# analog.net
KiCad netlist of a schematic drawn in EAGLE
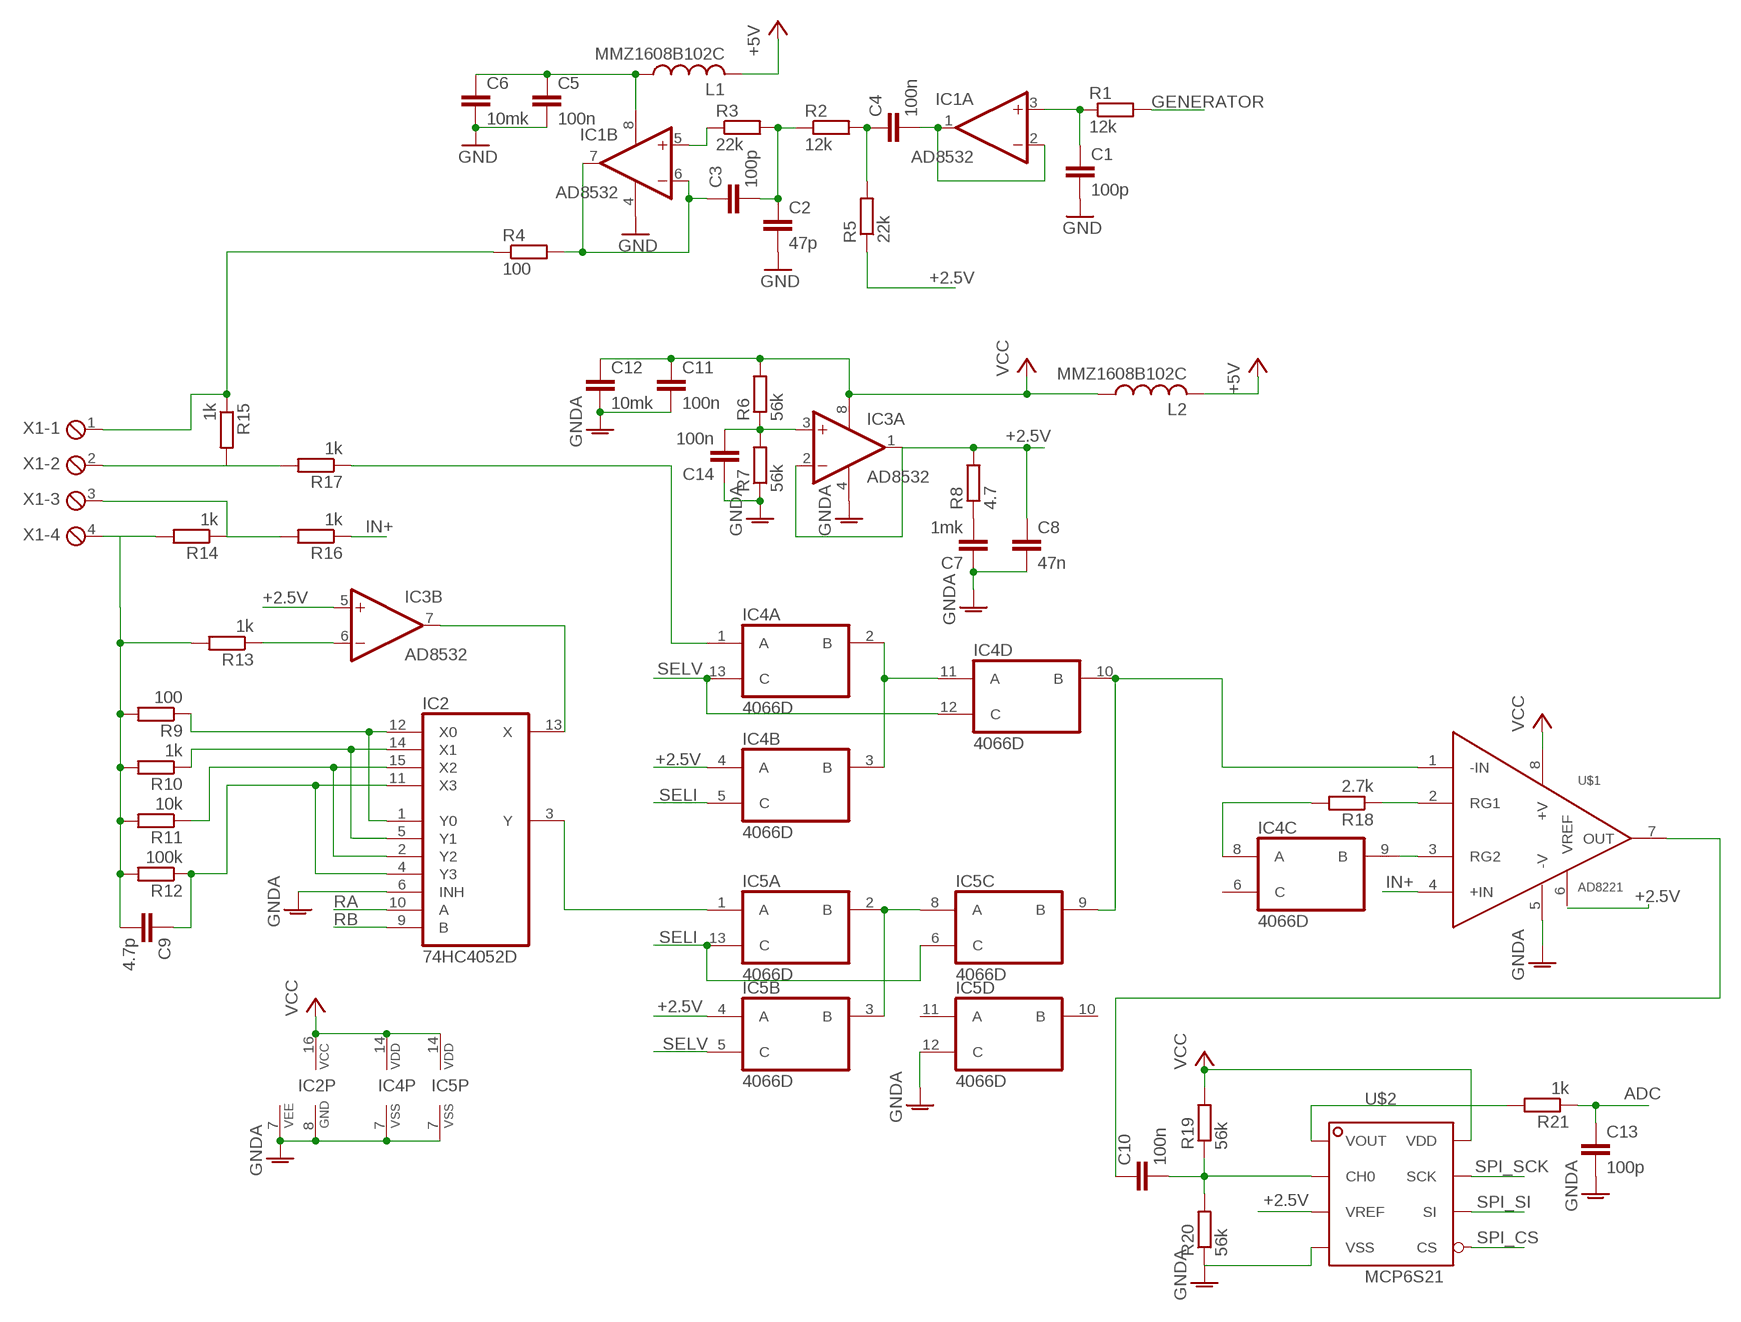
[diagram p0: schematic, sheet 1]

(export (version "E")
  (design (tool "Eeschema 10.0.6"))
  (components
    (comp (ref "C1")
      (value "100p")
      (footprint "eagle-import:C0805")
      (libsource (lib "eagle-import") (part "C-EUC0805"))
    )
    (comp (ref "C2")
      (value "47p")
      (footprint "eagle-import:C0805")
      (libsource (lib "eagle-import") (part "C-EUC0805"))
    )
    (comp (ref "C3")
      (value "100p")
      (footprint "eagle-import:C0805")
      (libsource (lib "eagle-import") (part "C-EUC0805"))
    )
    (comp (ref "C4")
      (value "100n")
      (footprint "eagle-import:C0603")
      (libsource (lib "eagle-import") (part "C-EUC0603"))
    )
    (comp (ref "C5")
      (value "100n")
      (footprint "eagle-import:C0603")
      (libsource (lib "eagle-import") (part "C-EUC0603"))
    )
    (comp (ref "C6")
      (value "10mk")
      (footprint "eagle-import:C0805")
      (libsource (lib "eagle-import") (part "C-EUC0805"))
    )
    (comp (ref "C7")
      (value "1mk")
      (footprint "eagle-import:C0603")
      (libsource (lib "eagle-import") (part "C-EUC0603"))
    )
    (comp (ref "C8")
      (value "47n")
      (footprint "eagle-import:C0805")
      (libsource (lib "eagle-import") (part "C-EUC0805"))
    )
    (comp (ref "C9")
      (value "4.7p")
      (footprint "eagle-import:C0805")
      (libsource (lib "eagle-import") (part "C-EUC0805"))
    )
    (comp (ref "C10")
      (value "100n")
      (footprint "eagle-import:C0603")
      (libsource (lib "eagle-import") (part "C-EUC0603"))
    )
    (comp (ref "C11")
      (value "100n")
      (footprint "eagle-import:C0603")
      (libsource (lib "eagle-import") (part "C-EUC0603"))
    )
    (comp (ref "C12")
      (value "10mk")
      (footprint "eagle-import:C0805")
      (libsource (lib "eagle-import") (part "C-EUC0805"))
    )
    (comp (ref "C13")
      (value "100p")
      (footprint "eagle-import:C0805")
      (libsource (lib "eagle-import") (part "C-EUC0805"))
    )
    (comp (ref "C14")
      (value "100n")
      (footprint "eagle-import:C0603")
      (libsource (lib "eagle-import") (part "C-EUC0603"))
    )
    (comp (ref "IC1")
      (value "AD8532")
      (footprint "eagle-import:SO08")
      (libsource (lib "eagle-import") (part "LM358D"))
    )
    (comp (ref "IC2")
      (value "74HC4052D")
      (footprint "eagle-import:SO16")
      (libsource (lib "eagle-import") (part "4052D"))
    )
    (comp (ref "IC3")
      (value "AD8532")
      (footprint "eagle-import:SO08")
      (libsource (lib "eagle-import") (part "LM358D"))
    )
    (comp (ref "IC4")
      (value "4066D")
      (footprint "eagle-import:SO14")
      (libsource (lib "eagle-import") (part "4066D"))
    )
    (comp (ref "IC5")
      (value "4066D")
      (footprint "eagle-import:SO14")
      (libsource (lib "eagle-import") (part "4066D"))
    )
    (comp (ref "L1")
      (value "MMZ1608B102C")
      (footprint "eagle-import:R0603")
      (libsource (lib "eagle-import") (part "L-US"))
    )
    (comp (ref "L2")
      (value "MMZ1608B102C")
      (footprint "eagle-import:R0603")
      (libsource (lib "eagle-import") (part "L-US"))
    )
    (comp (ref "R1")
      (value "12k")
      (footprint "eagle-import:R0805")
      (libsource (lib "eagle-import") (part "R-EU_R0805"))
    )
    (comp (ref "R2")
      (value "12k")
      (footprint "eagle-import:R0805")
      (libsource (lib "eagle-import") (part "R-EU_R0805"))
    )
    (comp (ref "R3")
      (value "22k")
      (footprint "eagle-import:R0805")
      (libsource (lib "eagle-import") (part "R-EU_R0805"))
    )
    (comp (ref "R4")
      (value "100")
      (footprint "eagle-import:R0805")
      (libsource (lib "eagle-import") (part "R-EU_R0805"))
    )
    (comp (ref "R5")
      (value "22k")
      (footprint "eagle-import:R0805")
      (libsource (lib "eagle-import") (part "R-EU_R0805"))
    )
    (comp (ref "R6")
      (value "56k")
      (footprint "eagle-import:R0805")
      (libsource (lib "eagle-import") (part "R-EU_R0805"))
    )
    (comp (ref "R7")
      (value "56k")
      (footprint "eagle-import:R0805")
      (libsource (lib "eagle-import") (part "R-EU_R0805"))
    )
    (comp (ref "R8")
      (value "4.7")
      (footprint "eagle-import:R0805")
      (libsource (lib "eagle-import") (part "R-EU_R0805"))
    )
    (comp (ref "R9")
      (value "100")
      (footprint "eagle-import:R0805")
      (libsource (lib "eagle-import") (part "R-EU_R0805"))
    )
    (comp (ref "R10")
      (value "1k")
      (footprint "eagle-import:R0805")
      (libsource (lib "eagle-import") (part "R-EU_R0805"))
    )
    (comp (ref "R11")
      (value "10k")
      (footprint "eagle-import:R0805")
      (libsource (lib "eagle-import") (part "R-EU_R0805"))
    )
    (comp (ref "R12")
      (value "100k")
      (footprint "eagle-import:R0805")
      (libsource (lib "eagle-import") (part "R-EU_R0805"))
    )
    (comp (ref "R13")
      (value "1k")
      (footprint "eagle-import:R0805")
      (libsource (lib "eagle-import") (part "R-EU_R0805"))
    )
    (comp (ref "R14")
      (value "1k")
      (footprint "eagle-import:R0805")
      (libsource (lib "eagle-import") (part "R-EU_R0805"))
    )
    (comp (ref "R15")
      (value "1k")
      (footprint "eagle-import:R0805")
      (libsource (lib "eagle-import") (part "R-EU_R0805"))
    )
    (comp (ref "R16")
      (value "1k")
      (footprint "eagle-import:R0805")
      (libsource (lib "eagle-import") (part "R-EU_R0805"))
    )
    (comp (ref "R17")
      (value "1k")
      (footprint "eagle-import:R0805")
      (libsource (lib "eagle-import") (part "R-EU_R0805"))
    )
    (comp (ref "R18")
      (value "2.7k")
      (footprint "eagle-import:R0805")
      (libsource (lib "eagle-import") (part "R-EU_R0805"))
    )
    (comp (ref "R19")
      (value "56k")
      (footprint "eagle-import:R0805")
      (libsource (lib "eagle-import") (part "R-EU_R0805"))
    )
    (comp (ref "R20")
      (value "56k")
      (footprint "eagle-import:R0805")
      (libsource (lib "eagle-import") (part "R-EU_R0805"))
    )
    (comp (ref "R21")
      (value "1k")
      (footprint "eagle-import:R0805")
      (libsource (lib "eagle-import") (part "R-EU_R0805"))
    )
    (comp (ref "U$1")
      (value "AD8221")
      (footprint "eagle-import:SSOP08")
      (libsource (lib "eagle-import") (part "AD8221"))
    )
    (comp (ref "U$2")
      (value "MCP6S21")
      (footprint "eagle-import:SO8")
      (libsource (lib "eagle-import") (part "MCP6S21"))
    )
    (comp (ref "X1")
      (value "MPT4")
      (footprint "eagle-import:4POL254")
      (libsource (lib "eagle-import") (part "MPT4"))
    )
  )
  (nets
    (net (code "1") (name "+5V") (class "Default")
      (node (ref "L1") (pin "2") (pinfunction "2_2") (pintype "passive"))
      (node (ref "L2") (pin "2") (pinfunction "2_2") (pintype "passive"))
    )
    (net (code "2") (name "/+2.5V") (class "Default")
      (node (ref "C8") (pin "1") (pinfunction "1_1") (pintype "passive"))
      (node (ref "IC3") (pin "1") (pinfunction "OUT_1") (pintype "output"))
      (node (ref "IC3") (pin "2") (pinfunction "-IN_2") (pintype "input"))
      (node (ref "IC3") (pin "5") (pinfunction "+IN_5") (pintype "input"))
      (node (ref "IC4") (pin "4") (pinfunction "A_4") (pintype "tri_state"))
      (node (ref "IC5") (pin "4") (pinfunction "A_4") (pintype "tri_state"))
      (node (ref "R5") (pin "1") (pinfunction "1_1") (pintype "passive"))
      (node (ref "R8") (pin "2") (pinfunction "2_2") (pintype "passive"))
      (node (ref "U$2") (pin "3") (pinfunction "VREF_3") (pintype "bidirectional"))
    )
    (net (code "3") (name "/ADC") (class "Default")
      (node (ref "C13") (pin "1") (pinfunction "1_1") (pintype "passive"))
      (node (ref "R21") (pin "1") (pinfunction "1_1") (pintype "passive"))
    )
    (net (code "4") (name "/GENERATOR") (class "Default")
      (node (ref "R1") (pin "2") (pinfunction "2_2") (pintype "passive"))
    )
    (net (code "5") (name "/IN+") (class "Default")
      (node (ref "R16") (pin "1") (pinfunction "1_1") (pintype "passive"))
      (node (ref "U$1") (pin "4") (pinfunction "+IN_4") (pintype "bidirectional"))
    )
    (net (code "6") (name "/RA") (class "Default")
      (node (ref "IC2") (pin "10") (pinfunction "A_10") (pintype "input"))
    )
    (net (code "7") (name "/RB") (class "Default")
      (node (ref "IC2") (pin "9") (pinfunction "B_9") (pintype "input"))
    )
    (net (code "8") (name "/SELI") (class "Default")
      (node (ref "IC4") (pin "5") (pinfunction "C_5") (pintype "input"))
      (node (ref "IC5") (pin "13") (pinfunction "C_13") (pintype "input"))
      (node (ref "IC5") (pin "6") (pinfunction "C_6") (pintype "input"))
    )
    (net (code "9") (name "/SELV") (class "Default")
      (node (ref "IC4") (pin "12") (pinfunction "C_12") (pintype "input"))
      (node (ref "IC4") (pin "13") (pinfunction "C_13") (pintype "input"))
      (node (ref "IC5") (pin "5") (pinfunction "C_5") (pintype "input"))
    )
    (net (code "10") (name "/SPI_CS") (class "Default")
      (node (ref "U$2") (pin "5") (pinfunction "CS_5") (pintype "bidirectional"))
    )
    (net (code "11") (name "/SPI_SCK") (class "Default")
      (node (ref "U$2") (pin "7") (pinfunction "SCK_7") (pintype "bidirectional"))
    )
    (net (code "12") (name "/SPI_SI") (class "Default")
      (node (ref "U$2") (pin "6") (pinfunction "SI_6") (pintype "bidirectional"))
    )
    (net (code "13") (name "GND") (class "Default")
      (node (ref "C1") (pin "2") (pinfunction "2_2") (pintype "passive"))
      (node (ref "C2") (pin "2") (pinfunction "2_2") (pintype "passive"))
      (node (ref "C5") (pin "2") (pinfunction "2_2") (pintype "passive"))
      (node (ref "C6") (pin "2") (pinfunction "2_2") (pintype "passive"))
      (node (ref "IC1") (pin "4") (pinfunction "V-_4") (pintype "power_in"))
    )
    (net (code "14") (name "GNDA") (class "Default")
      (node (ref "C11") (pin "2") (pinfunction "2_2") (pintype "passive"))
      (node (ref "C12") (pin "2") (pinfunction "2_2") (pintype "passive"))
      (node (ref "C13") (pin "2") (pinfunction "2_2") (pintype "passive"))
      (node (ref "C14") (pin "1") (pinfunction "1_1") (pintype "passive"))
      (node (ref "C7") (pin "1") (pinfunction "1_1") (pintype "passive"))
      (node (ref "C8") (pin "2") (pinfunction "2_2") (pintype "passive"))
      (node (ref "IC2") (pin "6") (pinfunction "INH_6") (pintype "input"))
      (node (ref "IC2") (pin "7") (pinfunction "VEE_7") (pintype "power_in"))
      (node (ref "IC2") (pin "8") (pinfunction "GND_8") (pintype "power_in"))
      (node (ref "IC3") (pin "4") (pinfunction "V-_4") (pintype "power_in"))
      (node (ref "IC4") (pin "7") (pinfunction "VSS_7") (pintype "power_in"))
      (node (ref "IC5") (pin "12") (pinfunction "C_12") (pintype "input"))
      (node (ref "IC5") (pin "7") (pinfunction "VSS_7") (pintype "power_in"))
      (node (ref "R20") (pin "1") (pinfunction "1_1") (pintype "passive"))
      (node (ref "R7") (pin "1") (pinfunction "1_1") (pintype "passive"))
      (node (ref "U$1") (pin "5") (pinfunction "-V_5") (pintype "bidirectional"))
      (node (ref "U$2") (pin "4") (pinfunction "VSS_4") (pintype "bidirectional"))
    )
    (net (code "15") (name "Net-(C2-Pad1)") (class "Default")
      (node (ref "C2") (pin "1") (pinfunction "1_1") (pintype "passive"))
      (node (ref "C3") (pin "2") (pinfunction "2_2") (pintype "passive"))
      (node (ref "R2") (pin "1") (pinfunction "1_1") (pintype "passive"))
      (node (ref "R3") (pin "2") (pinfunction "2_2") (pintype "passive"))
    )
    (net (code "16") (name "Net-(C4-Pad1)") (class "Default")
      (node (ref "C4") (pin "1") (pinfunction "1_1") (pintype "passive"))
      (node (ref "R2") (pin "2") (pinfunction "2_2") (pintype "passive"))
      (node (ref "R5") (pin "2") (pinfunction "2_2") (pintype "passive"))
    )
    (net (code "17") (name "Net-(C7-Pad2)") (class "Default")
      (node (ref "C7") (pin "2") (pinfunction "2_2") (pintype "passive"))
      (node (ref "R8") (pin "1") (pinfunction "1_1") (pintype "passive"))
    )
    (net (code "18") (name "Net-(IC1A-+IN)") (class "Default")
      (node (ref "C1") (pin "1") (pinfunction "1_1") (pintype "passive"))
      (node (ref "IC1") (pin "3") (pinfunction "+IN_3") (pintype "input"))
      (node (ref "R1") (pin "1") (pinfunction "1_1") (pintype "passive"))
    )
    (net (code "19") (name "Net-(IC1A--IN)") (class "Default")
      (node (ref "C4") (pin "2") (pinfunction "2_2") (pintype "passive"))
      (node (ref "IC1") (pin "1") (pinfunction "OUT_1") (pintype "output"))
      (node (ref "IC1") (pin "2") (pinfunction "-IN_2") (pintype "input"))
    )
    (net (code "20") (name "Net-(IC1B-+IN)") (class "Default")
      (node (ref "IC1") (pin "5") (pinfunction "+IN_5") (pintype "input"))
      (node (ref "R3") (pin "1") (pinfunction "1_1") (pintype "passive"))
    )
    (net (code "21") (name "Net-(IC1B--IN)") (class "Default")
      (node (ref "C3") (pin "1") (pinfunction "1_1") (pintype "passive"))
      (node (ref "IC1") (pin "6") (pinfunction "-IN_6") (pintype "input"))
      (node (ref "IC1") (pin "7") (pinfunction "OUT_7") (pintype "output"))
      (node (ref "R4") (pin "2") (pinfunction "2_2") (pintype "passive"))
    )
    (net (code "22") (name "Net-(IC1C-V+)") (class "Default")
      (node (ref "C5") (pin "1") (pinfunction "1_1") (pintype "passive"))
      (node (ref "C6") (pin "1") (pinfunction "1_1") (pintype "passive"))
      (node (ref "IC1") (pin "8") (pinfunction "V+_8") (pintype "power_in"))
      (node (ref "L1") (pin "1") (pinfunction "1_1") (pintype "passive"))
    )
    (net (code "23") (name "Net-(IC2A-X)") (class "Default")
      (node (ref "IC2") (pin "13") (pinfunction "X_13") (pintype "bidirectional"))
      (node (ref "IC3") (pin "7") (pinfunction "OUT_7") (pintype "output"))
    )
    (net (code "24") (name "Net-(IC2A-X0)") (class "Default")
      (node (ref "IC2") (pin "1") (pinfunction "Y0_1") (pintype "bidirectional"))
      (node (ref "IC2") (pin "12") (pinfunction "X0_12") (pintype "bidirectional"))
      (node (ref "R9") (pin "1") (pinfunction "1_1") (pintype "passive"))
    )
    (net (code "25") (name "Net-(IC2A-X1)") (class "Default")
      (node (ref "IC2") (pin "14") (pinfunction "X1_14") (pintype "bidirectional"))
      (node (ref "IC2") (pin "5") (pinfunction "Y1_5") (pintype "bidirectional"))
      (node (ref "R10") (pin "1") (pinfunction "1_1") (pintype "passive"))
    )
    (net (code "26") (name "Net-(IC2A-X2)") (class "Default")
      (node (ref "IC2") (pin "15") (pinfunction "X2_15") (pintype "bidirectional"))
      (node (ref "IC2") (pin "2") (pinfunction "Y2_2") (pintype "bidirectional"))
      (node (ref "R11") (pin "1") (pinfunction "1_1") (pintype "passive"))
    )
    (net (code "27") (name "Net-(IC2A-X3)") (class "Default")
      (node (ref "C9") (pin "1") (pinfunction "1_1") (pintype "passive"))
      (node (ref "IC2") (pin "11") (pinfunction "X3_11") (pintype "bidirectional"))
      (node (ref "IC2") (pin "4") (pinfunction "Y3_4") (pintype "bidirectional"))
      (node (ref "R12") (pin "1") (pinfunction "1_1") (pintype "passive"))
    )
    (net (code "28") (name "Net-(IC2A-Y)") (class "Default")
      (node (ref "IC2") (pin "3") (pinfunction "Y_3") (pintype "bidirectional"))
      (node (ref "IC5") (pin "1") (pinfunction "A_1") (pintype "tri_state"))
    )
    (net (code "29") (name "Net-(IC3A-+IN)") (class "Default")
      (node (ref "C14") (pin "2") (pinfunction "2_2") (pintype "passive"))
      (node (ref "IC3") (pin "3") (pinfunction "+IN_3") (pintype "input"))
      (node (ref "R6") (pin "1") (pinfunction "1_1") (pintype "passive"))
      (node (ref "R7") (pin "2") (pinfunction "2_2") (pintype "passive"))
    )
    (net (code "30") (name "Net-(IC3B--IN)") (class "Default")
      (node (ref "IC3") (pin "6") (pinfunction "-IN_6") (pintype "input"))
      (node (ref "R13") (pin "1") (pinfunction "1_1") (pintype "passive"))
    )
    (net (code "31") (name "Net-(IC4A-A)") (class "Default")
      (node (ref "IC4") (pin "1") (pinfunction "A_1") (pintype "tri_state"))
      (node (ref "R17") (pin "1") (pinfunction "1_1") (pintype "passive"))
    )
    (net (code "32") (name "Net-(IC4A-B)") (class "Default")
      (node (ref "IC4") (pin "11") (pinfunction "A_11") (pintype "tri_state"))
      (node (ref "IC4") (pin "2") (pinfunction "B_2") (pintype "tri_state"))
      (node (ref "IC4") (pin "3") (pinfunction "B_3") (pintype "tri_state"))
    )
    (net (code "33") (name "Net-(IC4C-A)") (class "Default")
      (node (ref "IC4") (pin "8") (pinfunction "A_8") (pintype "tri_state"))
      (node (ref "R18") (pin "2") (pinfunction "2_2") (pintype "passive"))
    )
    (net (code "34") (name "Net-(IC4C-B)") (class "Default")
      (node (ref "IC4") (pin "9") (pinfunction "B_9") (pintype "tri_state"))
      (node (ref "U$1") (pin "3") (pinfunction "RG2_3") (pintype "bidirectional"))
    )
    (net (code "35") (name "Net-(IC4D-B)") (class "Default")
      (node (ref "IC4") (pin "10") (pinfunction "B_10") (pintype "tri_state"))
      (node (ref "IC5") (pin "9") (pinfunction "B_9") (pintype "tri_state"))
      (node (ref "U$1") (pin "1") (pinfunction "-IN_1") (pintype "bidirectional"))
    )
    (net (code "36") (name "Net-(IC5A-B)") (class "Default")
      (node (ref "IC5") (pin "2") (pinfunction "B_2") (pintype "tri_state"))
      (node (ref "IC5") (pin "3") (pinfunction "B_3") (pintype "tri_state"))
      (node (ref "IC5") (pin "8") (pinfunction "A_8") (pintype "tri_state"))
    )
    (net (code "37") (name "Net-(R15-Pad1)") (class "Default")
      (node (ref "R15") (pin "1") (pinfunction "1_1") (pintype "passive"))
      (node (ref "R4") (pin "1") (pinfunction "1_1") (pintype "passive"))
      (node (ref "X1") (pin "1") (pinfunction "1_1") (pintype "passive"))
    )
    (net (code "38") (name "Net-(U$1-OUT)") (class "Default")
      (node (ref "C10") (pin "1") (pinfunction "1_1") (pintype "passive"))
      (node (ref "U$1") (pin "7") (pinfunction "OUT_7") (pintype "bidirectional"))
    )
    (net (code "39") (name "Net-(U$1-RG1)") (class "Default")
      (node (ref "R18") (pin "1") (pinfunction "1_1") (pintype "passive"))
      (node (ref "U$1") (pin "2") (pinfunction "RG1_2") (pintype "bidirectional"))
    )
    (net (code "40") (name "Net-(U$2-CH0)") (class "Default")
      (node (ref "C10") (pin "2") (pinfunction "2_2") (pintype "passive"))
      (node (ref "R19") (pin "1") (pinfunction "1_1") (pintype "passive"))
      (node (ref "R20") (pin "2") (pinfunction "2_2") (pintype "passive"))
      (node (ref "U$2") (pin "2") (pinfunction "CH0_2") (pintype "bidirectional"))
    )
    (net (code "41") (name "Net-(U$2-VOUT)") (class "Default")
      (node (ref "R21") (pin "2") (pinfunction "2_2") (pintype "passive"))
      (node (ref "U$2") (pin "1") (pinfunction "VOUT_1") (pintype "output"))
    )
    (net (code "42") (name "Net-(X1B-1)") (class "Default")
      (node (ref "R15") (pin "2") (pinfunction "2_2") (pintype "passive"))
      (node (ref "R17") (pin "2") (pinfunction "2_2") (pintype "passive"))
      (node (ref "X1") (pin "2") (pinfunction "1_2") (pintype "passive"))
    )
    (net (code "43") (name "Net-(X1C-1)") (class "Default")
      (node (ref "R14") (pin "1") (pinfunction "1_1") (pintype "passive"))
      (node (ref "R16") (pin "2") (pinfunction "2_2") (pintype "passive"))
      (node (ref "X1") (pin "3") (pinfunction "1_3") (pintype "passive"))
    )
    (net (code "44") (name "Net-(X1D-1)") (class "Default")
      (node (ref "C9") (pin "2") (pinfunction "2_2") (pintype "passive"))
      (node (ref "R10") (pin "2") (pinfunction "2_2") (pintype "passive"))
      (node (ref "R11") (pin "2") (pinfunction "2_2") (pintype "passive"))
      (node (ref "R12") (pin "2") (pinfunction "2_2") (pintype "passive"))
      (node (ref "R13") (pin "2") (pinfunction "2_2") (pintype "passive"))
      (node (ref "R14") (pin "2") (pinfunction "2_2") (pintype "passive"))
      (node (ref "R9") (pin "2") (pinfunction "2_2") (pintype "passive"))
      (node (ref "X1") (pin "4") (pinfunction "1_4") (pintype "passive"))
    )
    (net (code "45") (name "VCC") (class "Default")
      (node (ref "C11") (pin "1") (pinfunction "1_1") (pintype "passive"))
      (node (ref "C12") (pin "1") (pinfunction "1_1") (pintype "passive"))
      (node (ref "IC2") (pin "16") (pinfunction "VCC_16") (pintype "power_in"))
      (node (ref "IC3") (pin "8") (pinfunction "V+_8") (pintype "power_in"))
      (node (ref "IC4") (pin "14") (pinfunction "VDD_14") (pintype "power_in"))
      (node (ref "IC5") (pin "14") (pinfunction "VDD_14") (pintype "power_in"))
      (node (ref "L2") (pin "1") (pinfunction "1_1") (pintype "passive"))
      (node (ref "R19") (pin "2") (pinfunction "2_2") (pintype "passive"))
      (node (ref "R6") (pin "2") (pinfunction "2_2") (pintype "passive"))
      (node (ref "U$1") (pin "8") (pinfunction "+V_8") (pintype "bidirectional"))
      (node (ref "U$2") (pin "8") (pinfunction "VDD_8") (pintype "bidirectional"))
    )
    (net (code "46") (name "unconnected-(IC4C-C-Pad6)") (class "Default")
      (node (ref "IC4") (pin "6") (pinfunction "C_6") (pintype "input"))
    )
    (net (code "47") (name "unconnected-(IC5D-A-Pad11)") (class "Default")
      (node (ref "IC5") (pin "11") (pinfunction "A_11") (pintype "tri_state"))
    )
    (net (code "48") (name "unconnected-(IC5D-B-Pad10)") (class "Default")
      (node (ref "IC5") (pin "10") (pinfunction "B_10") (pintype "tri_state"))
    )
    (net (code "49") (name "unconnected-(U$1-VREF-Pad6)") (class "Default")
      (node (ref "U$1") (pin "6") (pinfunction "VREF_6") (pintype "bidirectional"))
    )
  )
)
